# BAT_INDICATOR.net
KiCad netlist of a schematic drawn in Altium Designer
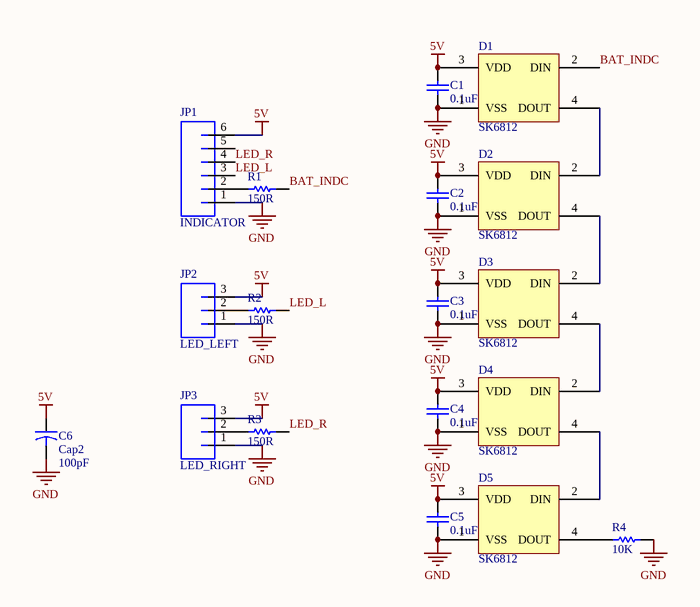
[diagram p0: BAT_INDICATOR.SchDoc]

(export (version "E")
  (design (tool "Eeschema 10.0.6"))
  (components
    (comp (ref "C1")
      (value "0.1uF")
      (footprint "C0603[1608X92]")
      (description "0.1uF 16V 10% 0603 (1608 Metric)")
      (fields (field (name "PARTNUMBER") "GCM188R71C104KA37D") (field (name "MANUFACTURER") "Murata"))
      (libsource (lib "Capacitors") (part "CAP_0.1uF_16V_0603_10%"))
    )
    (comp (ref "C2")
      (value "0.1uF")
      (footprint "C0603[1608X92]")
      (description "0.1uF 16V 10% 0603 (1608 Metric)")
      (fields (field (name "PARTNUMBER") "GCM188R71C104KA37D") (field (name "MANUFACTURER") "Murata"))
      (libsource (lib "Capacitors") (part "CAP_0.1uF_16V_0603_10%"))
    )
    (comp (ref "C3")
      (value "0.1uF")
      (footprint "C0603[1608X92]")
      (description "0.1uF 16V 10% 0603 (1608 Metric)")
      (fields (field (name "PARTNUMBER") "GCM188R71C104KA37D") (field (name "MANUFACTURER") "Murata"))
      (libsource (lib "Capacitors") (part "CAP_0.1uF_16V_0603_10%"))
    )
    (comp (ref "C4")
      (value "0.1uF")
      (footprint "C0603[1608X92]")
      (description "0.1uF 16V 10% 0603 (1608 Metric)")
      (fields (field (name "PARTNUMBER") "GCM188R71C104KA37D") (field (name "MANUFACTURER") "Murata"))
      (libsource (lib "Capacitors") (part "CAP_0.1uF_16V_0603_10%"))
    )
    (comp (ref "C5")
      (value "0.1uF")
      (footprint "C0603[1608X92]")
      (description "0.1uF 16V 10% 0603 (1608 Metric)")
      (fields (field (name "PARTNUMBER") "GCM188R71C104KA37D") (field (name "MANUFACTURER") "Murata"))
      (libsource (lib "Capacitors") (part "CAP_0.1uF_16V_0603_10%"))
    )
    (comp (ref "C6")
      (value "Cap2")
      (footprint "CAPR5-4X5")
      (description "Capacitor")
      (fields (field (name "ALTIUM_VALUE") "100pF") (field (name "PUBLISHER") "Altium Limited"))
      (libsource (lib "Miscellaneous Devices") (part "Cap2"))
    )
    (comp (ref "D1")
      (value "SK6812")
      (footprint "SK6812")
      (description "smart control circuit and a light emitting circuit in one of the controlled LED source")
      (libsource (lib "LEDs") (part "SK6812"))
    )
    (comp (ref "D2")
      (value "SK6812")
      (footprint "SK6812")
      (description "smart control circuit and a light emitting circuit in one of the controlled LED source")
      (libsource (lib "LEDs") (part "SK6812"))
    )
    (comp (ref "D3")
      (value "SK6812")
      (footprint "SK6812")
      (description "smart control circuit and a light emitting circuit in one of the controlled LED source")
      (libsource (lib "LEDs") (part "SK6812"))
    )
    (comp (ref "D4")
      (value "SK6812")
      (footprint "SK6812")
      (description "smart control circuit and a light emitting circuit in one of the controlled LED source")
      (libsource (lib "LEDs") (part "SK6812"))
    )
    (comp (ref "D5")
      (value "SK6812")
      (footprint "SK6812")
      (description "smart control circuit and a light emitting circuit in one of the controlled LED source")
      (libsource (lib "LEDs") (part "SK6812"))
    )
    (comp (ref "JP1")
      (value "INDICATOR")
      (footprint "JST-PH-6-PTH-VERT")
      (fields
        (field (name "PARTNUMBER") "B6B-PH-K-S(LF)(SN)")
        (field (name "MANUFACTURER") "JST Sales America Inc.")
      )
      (libsource (lib "Connectors") (part "JST_PH_6_VERT"))
    )
    (comp (ref "JP2")
      (value "LED_LEFT")
      (footprint "JST-PH-3-PTH-VERT")
      (fields
        (field (name "MANUFACTURER") "JST Sales America Inc.")
        (field (name "PARTNUMBER") "B3B-PH-K-S(LF)(SN)")
      )
      (libsource (lib "Connectors") (part "JST_PH_3_VERT"))
    )
    (comp (ref "JP3")
      (value "LED_RIGHT")
      (footprint "JST-PH-3-PTH-VERT")
      (fields
        (field (name "MANUFACTURER") "JST Sales America Inc.")
        (field (name "PARTNUMBER") "B3B-PH-K-S(LF)(SN)")
      )
      (libsource (lib "Connectors") (part "JST_PH_3_VERT"))
    )
    (comp (ref "R1")
      (value "150R")
      (footprint "R0603[1608]")
      (description "150R 0.25W 1% 0603 (1005 Metric)")
      (fields (field (name "MANUFACTURER") "Vishay / Dale") (field (name "PARTNUMBER") "CRCW0603150RFKEAHP"))
      (libsource (lib "Resistors") (part "RES_150R_0603_1%"))
    )
    (comp (ref "R2")
      (value "150R")
      (footprint "R0603[1608]")
      (description "150R 0.25W 1% 0603 (1005 Metric)")
      (fields (field (name "MANUFACTURER") "Vishay / Dale") (field (name "PARTNUMBER") "CRCW0603150RFKEAHP"))
      (libsource (lib "Resistors") (part "RES_150R_0603_1%"))
    )
    (comp (ref "R3")
      (value "150R")
      (footprint "R0603[1608]")
      (description "150R 0.25W 1% 0603 (1005 Metric)")
      (fields (field (name "MANUFACTURER") "Vishay / Dale") (field (name "PARTNUMBER") "CRCW0603150RFKEAHP"))
      (libsource (lib "Resistors") (part "RES_150R_0603_1%"))
    )
    (comp (ref "R4")
      (value "10K")
      (footprint "R0603[1608]")
      (description "10K 0.25W 1% 0603 (1005 Metric)")
      (fields (field (name "MANUFACTURER") "Vishay / Dale") (field (name "PARTNUMBER") "CRCW060310K0FKEAHP"))
      (libsource (lib "Resistors") (part "RES_10K_0603_1%"))
    )
  )
  (nets
    (net (code "1") (name "/BAT_INDC") (class "Default")
      (node (ref "D1") (pin "2") (pinfunction "DIN_2") (pintype "passive"))
      (node (ref "R1") (pin "2") (pinfunction "2_2") (pintype "passive"))
    )
    (net (code "2") (name "/LED_L") (class "Default")
      (node (ref "JP1") (pin "3") (pinfunction "3_3") (pintype "passive"))
      (node (ref "R2") (pin "2") (pinfunction "2_2") (pintype "passive"))
    )
    (net (code "3") (name "/LED_R") (class "Default")
      (node (ref "JP1") (pin "4") (pinfunction "4_4") (pintype "passive"))
      (node (ref "R3") (pin "2") (pinfunction "2_2") (pintype "passive"))
    )
    (net (code "4") (name "5V") (class "Default")
      (node (ref "C1") (pin "2") (pinfunction "2_2") (pintype "passive"))
      (node (ref "C2") (pin "2") (pinfunction "2_2") (pintype "passive"))
      (node (ref "C3") (pin "2") (pinfunction "2_2") (pintype "passive"))
      (node (ref "C4") (pin "2") (pinfunction "2_2") (pintype "passive"))
      (node (ref "C5") (pin "2") (pinfunction "2_2") (pintype "passive"))
      (node (ref "C6") (pin "1") (pinfunction "1_1") (pintype "passive"))
      (node (ref "D1") (pin "3") (pinfunction "VDD_3") (pintype "passive"))
      (node (ref "D2") (pin "3") (pinfunction "VDD_3") (pintype "passive"))
      (node (ref "D3") (pin "3") (pinfunction "VDD_3") (pintype "passive"))
      (node (ref "D4") (pin "3") (pinfunction "VDD_3") (pintype "passive"))
      (node (ref "D5") (pin "3") (pinfunction "VDD_3") (pintype "passive"))
      (node (ref "JP1") (pin "6") (pinfunction "6_6") (pintype "passive"))
      (node (ref "JP2") (pin "3") (pinfunction "3_3") (pintype "passive"))
      (node (ref "JP3") (pin "3") (pinfunction "3_3") (pintype "passive"))
    )
    (net (code "5") (name "GND") (class "Default")
      (node (ref "C1") (pin "1") (pinfunction "1_1") (pintype "passive"))
      (node (ref "C2") (pin "1") (pinfunction "1_1") (pintype "passive"))
      (node (ref "C3") (pin "1") (pinfunction "1_1") (pintype "passive"))
      (node (ref "C4") (pin "1") (pinfunction "1_1") (pintype "passive"))
      (node (ref "C5") (pin "1") (pinfunction "1_1") (pintype "passive"))
      (node (ref "C6") (pin "2") (pinfunction "2_2") (pintype "passive"))
      (node (ref "D1") (pin "1") (pinfunction "VSS_1") (pintype "passive"))
      (node (ref "D2") (pin "1") (pinfunction "VSS_1") (pintype "passive"))
      (node (ref "D3") (pin "1") (pinfunction "VSS_1") (pintype "passive"))
      (node (ref "D4") (pin "1") (pinfunction "VSS_1") (pintype "passive"))
      (node (ref "D5") (pin "1") (pinfunction "VSS_1") (pintype "passive"))
      (node (ref "JP1") (pin "1") (pinfunction "1_1") (pintype "passive"))
      (node (ref "JP2") (pin "1") (pinfunction "1_1") (pintype "passive"))
      (node (ref "JP3") (pin "1") (pinfunction "1_1") (pintype "passive"))
      (node (ref "R4") (pin "1") (pinfunction "1_1") (pintype "passive"))
    )
    (net (code "6") (name "Net-(D1-DOUT)") (class "Default")
      (node (ref "D1") (pin "4") (pinfunction "DOUT_4") (pintype "passive"))
      (node (ref "D2") (pin "2") (pinfunction "DIN_2") (pintype "passive"))
    )
    (net (code "7") (name "Net-(D2-DOUT)") (class "Default")
      (node (ref "D2") (pin "4") (pinfunction "DOUT_4") (pintype "passive"))
      (node (ref "D3") (pin "2") (pinfunction "DIN_2") (pintype "passive"))
    )
    (net (code "8") (name "Net-(D3-DOUT)") (class "Default")
      (node (ref "D3") (pin "4") (pinfunction "DOUT_4") (pintype "passive"))
      (node (ref "D4") (pin "2") (pinfunction "DIN_2") (pintype "passive"))
    )
    (net (code "9") (name "Net-(D4-DOUT)") (class "Default")
      (node (ref "D4") (pin "4") (pinfunction "DOUT_4") (pintype "passive"))
      (node (ref "D5") (pin "2") (pinfunction "DIN_2") (pintype "passive"))
    )
    (net (code "10") (name "Net-(D5-DOUT)") (class "Default")
      (node (ref "D5") (pin "4") (pinfunction "DOUT_4") (pintype "passive"))
      (node (ref "R4") (pin "2") (pinfunction "2_2") (pintype "passive"))
    )
    (net (code "11") (name "Net-(JP1-Pad2)") (class "Default")
      (node (ref "JP1") (pin "2") (pinfunction "2_2") (pintype "passive"))
      (node (ref "R1") (pin "1") (pinfunction "1_1") (pintype "passive"))
    )
    (net (code "12") (name "Net-(JP2-Pad2)") (class "Default")
      (node (ref "JP2") (pin "2") (pinfunction "2_2") (pintype "passive"))
      (node (ref "R2") (pin "1") (pinfunction "1_1") (pintype "passive"))
    )
    (net (code "13") (name "Net-(JP3-Pad2)") (class "Default")
      (node (ref "JP3") (pin "2") (pinfunction "2_2") (pintype "passive"))
      (node (ref "R3") (pin "1") (pinfunction "1_1") (pintype "passive"))
    )
    (net (code "14") (name "unconnected-(JP1-Pad5)") (class "Default")
      (node (ref "JP1") (pin "5") (pinfunction "5_5") (pintype "passive"))
    )
  )
)
